# Sheet1.net
KiCad netlist of a schematic drawn in Altium Designer
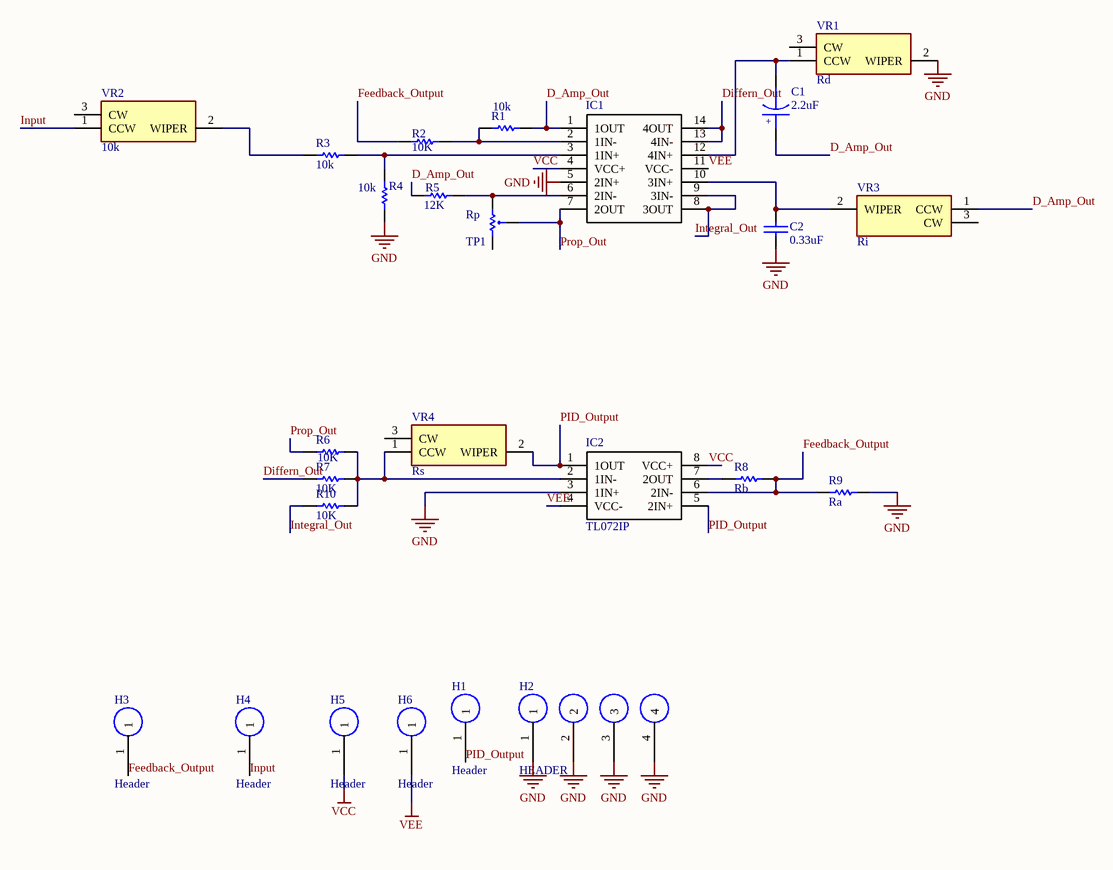
[diagram p0: Sheet1.SchDoc]

(export (version "E")
  (design (tool "Eeschema 10.0.6"))
  (components
    (comp (ref "C1")
      (value "2.2uF")
      (footprint "PCB_Project_PCBparts:RB.1/.2")
      (description "Polarized Cap")
      (libsource (lib "PCB_Project_SCHparts") (part "CAPACITOR POL"))
    )
    (comp (ref "C2")
      (value "0.33uF")
      (footprint "PCB_Project_PCBparts:RAD0.1")
      (description "Non Polarized Cap")
      (libsource (lib "PCB_Project_SCHparts") (part "CAP"))
    )
    (comp (ref "H1")
      (value "Header")
      (footprint "HEADER SINGLE")
      (description "Header single")
      (libsource (lib "PCB_Project_SCHparts") (part "HEADER 1"))
    )
    (comp (ref "H2")
      (value "HEADER")
      (footprint "HEADER QUAD")
      (description "Header quad")
      (libsource (lib "PCB_Project_SCHparts") (part "HEADER 4"))
    )
    (comp (ref "H3")
      (value "Header")
      (footprint "HEADER SINGLE")
      (description "Header single")
      (libsource (lib "PCB_Project_SCHparts") (part "HEADER 1"))
    )
    (comp (ref "H4")
      (value "Header")
      (footprint "HEADER SINGLE")
      (description "Header single")
      (libsource (lib "PCB_Project_SCHparts") (part "HEADER 1"))
    )
    (comp (ref "H5")
      (value "Header")
      (footprint "HEADER SINGLE")
      (description "Header single")
      (libsource (lib "PCB_Project_SCHparts") (part "HEADER 1"))
    )
    (comp (ref "H6")
      (value "Header")
      (footprint "HEADER SINGLE")
      (description "Header single")
      (libsource (lib "PCB_Project_SCHparts") (part "HEADER 1"))
    )
    (comp (ref "IC1")
      (value "~")
      (footprint "DIP794W53P254L1930H508Q14N")
      (description "Integrated Circuit")
      (fields
        (field (name "MANUFACTURER_PART_NUMBER") "TL074CN")
        (field (name "MOUSER PART NUMBER") "511-TL074CN")
      )
      (libsource (lib "PCB_Project_SCHparts_2") (part "TL074CN"))
    )
    (comp (ref "IC2")
      (value "TL072IP")
      (footprint "DIP794W53P254L959H508Q8N")
      (description "Integrated Circuit")
      (fields (field (name "MOUSER PART NUMBER") "595-TL072IP"))
      (libsource (lib "PCB_Project_SCHparts_2") (part "TL072IP"))
    )
    (comp (ref "R1")
      (value "10k")
      (footprint "PCB_Project_PCBparts:AXIAL0.4")
      (description "1/4 W Res")
      (libsource (lib "PCB_Project_SCHparts") (part "RES"))
    )
    (comp (ref "R2")
      (value "10K")
      (footprint "PCB_Project_PCBparts:AXIAL0.4")
      (description "1/4 W Res")
      (libsource (lib "PCB_Project_SCHparts") (part "RES"))
    )
    (comp (ref "R3")
      (value "10k")
      (footprint "PCB_Project_PCBparts:AXIAL0.4")
      (description "1/4 W Res")
      (libsource (lib "PCB_Project_SCHparts") (part "RES"))
    )
    (comp (ref "R4")
      (value "10k")
      (footprint "PCB_Project_PCBparts:AXIAL0.4")
      (description "1/4 W Res")
      (libsource (lib "PCB_Project_SCHparts") (part "RES"))
    )
    (comp (ref "R5")
      (value "12K")
      (footprint "PCB_Project_PCBparts:AXIAL0.4")
      (description "1/4 W Res")
      (libsource (lib "PCB_Project_SCHparts") (part "RES"))
    )
    (comp (ref "R6")
      (value "10K")
      (footprint "PCB_Project_PCBparts:AXIAL0.4")
      (description "1/4 W Res")
      (libsource (lib "PCB_Project_SCHparts") (part "RES"))
    )
    (comp (ref "R7")
      (value "10K")
      (footprint "PCB_Project_PCBparts:AXIAL0.4")
      (description "1/4 W Res")
      (libsource (lib "PCB_Project_SCHparts") (part "RES"))
    )
    (comp (ref "R8")
      (value "Rb")
      (footprint "PCB_Project_PCBparts:AXIAL0.4")
      (description "1/4 W Res")
      (libsource (lib "PCB_Project_SCHparts") (part "RES"))
    )
    (comp (ref "R9")
      (value "Ra")
      (footprint "PCB_Project_PCBparts:AXIAL0.4")
      (description "1/4 W Res")
      (libsource (lib "PCB_Project_SCHparts") (part "RES"))
    )
    (comp (ref "R10")
      (value "10K")
      (footprint "PCB_Project_PCBparts:AXIAL0.4")
      (description "1/4 W Res")
      (libsource (lib "PCB_Project_SCHparts") (part "RES"))
    )
    (comp (ref "TP1")
      (value "Rp")
      (footprint "TRIMPOT")
      (description "Rp=250K")
      (libsource (lib "PCB_Project_SCHparts") (part "TRIMPOT"))
    )
    (comp (ref "VR1")
      (value "Rd")
      (footprint "3386F1104TLF")
      (description "Variable Resistor")
      (fields
        (field (name "MANUFACTURER_PART_NUMBER") "3386F-1-104TLF")
        (field (name "MOUSER PART NUMBER") "652-3386F-1-104TLF")
      )
      (libsource (lib "PCB_Project_SCHparts_2") (part "3386F-1-104TLF"))
    )
    (comp (ref "VR2")
      (value "10k")
      (footprint "3386F1104TLF")
      (description "Variable Resistor")
      (fields
        (field (name "MANUFACTURER_PART_NUMBER") "3386F-1-104TLF")
        (field (name "MOUSER PART NUMBER") "652-3386F-1-104TLF")
      )
      (libsource (lib "PCB_Project_SCHparts_2") (part "3386F-1-104TLF"))
    )
    (comp (ref "VR3")
      (value "Ri")
      (footprint "PCB_Project_PCBparts_2:3386F1104TLF")
      (description "Variable Resistor")
      (fields
        (field (name "MANUFACTURER_PART_NUMBER") "3386F-1-104TLF")
        (field (name "MOUSER PART NUMBER") "652-3386F-1-104TLF")
      )
      (libsource (lib "") (part "3386F-1-104TLF_1"))
    )
    (comp (ref "VR4")
      (value "Rs")
      (footprint "3386F1104TLF")
      (description "Variable Resistor")
      (fields
        (field (name "MANUFACTURER_PART_NUMBER") "3386F-1-104TLF")
        (field (name "MOUSER PART NUMBER") "652-3386F-1-104TLF")
      )
      (libsource (lib "PCB_Project_SCHparts_2") (part "3386F-1-104TLF"))
    )
  )
  (nets
    (net (code "1") (name "/D_Amp_Out") (class "Default")
      (node (ref "C1") (pin "1") (pinfunction "1_1") (pintype "passive"))
      (node (ref "IC1") (pin "1") (pinfunction "1OUT_1") (pintype "passive"))
      (node (ref "R1") (pin "2") (pinfunction "2_2") (pintype "passive"))
      (node (ref "R5") (pin "1") (pinfunction "1_1") (pintype "passive"))
      (node (ref "VR3") (pin "1") (pinfunction "CCW_1") (pintype "passive"))
    )
    (net (code "2") (name "/Differn_Out") (class "Default")
      (node (ref "IC1") (pin "13") (pinfunction "4IN-_13") (pintype "passive"))
      (node (ref "IC1") (pin "14") (pinfunction "4OUT_14") (pintype "passive"))
      (node (ref "R7") (pin "1") (pinfunction "1_1") (pintype "passive"))
    )
    (net (code "3") (name "/Feedback_Output") (class "Default")
      (node (ref "H3") (pin "1") (pinfunction "1_1") (pintype "passive"))
      (node (ref "IC2") (pin "6") (pinfunction "2IN-_6") (pintype "passive"))
      (node (ref "R2") (pin "1") (pinfunction "1_1") (pintype "passive"))
      (node (ref "R8") (pin "2") (pinfunction "2_2") (pintype "passive"))
      (node (ref "R9") (pin "1") (pinfunction "1_1") (pintype "passive"))
    )
    (net (code "4") (name "/Input") (class "Default")
      (node (ref "H4") (pin "1") (pinfunction "1_1") (pintype "passive"))
      (node (ref "VR2") (pin "1") (pinfunction "CCW_1") (pintype "passive"))
    )
    (net (code "5") (name "/Integral_Out") (class "Default")
      (node (ref "IC1") (pin "8") (pinfunction "3OUT_8") (pintype "passive"))
      (node (ref "IC1") (pin "9") (pinfunction "3IN-_9") (pintype "passive"))
      (node (ref "R10") (pin "1") (pinfunction "1_1") (pintype "passive"))
    )
    (net (code "6") (name "/PID_Output") (class "Default")
      (node (ref "H1") (pin "1") (pinfunction "1_1") (pintype "passive"))
      (node (ref "IC2") (pin "1") (pinfunction "1OUT_1") (pintype "passive"))
      (node (ref "IC2") (pin "5") (pinfunction "2IN+_5") (pintype "passive"))
      (node (ref "VR4") (pin "2") (pinfunction "WIPER_2") (pintype "passive"))
    )
    (net (code "7") (name "/Prop_Out") (class "Default")
      (node (ref "IC1") (pin "7") (pinfunction "2OUT_7") (pintype "passive"))
      (node (ref "R6") (pin "1") (pinfunction "1_1") (pintype "passive"))
      (node (ref "TP1") (pin "2") (pinfunction "2_2") (pintype "passive"))
    )
    (net (code "8") (name "GND") (class "Default")
      (node (ref "C2") (pin "1") (pintype "passive"))
      (node (ref "H2") (pin "1") (pinfunction "1_1") (pintype "passive"))
      (node (ref "H2") (pin "2") (pinfunction "2_2") (pintype "passive"))
      (node (ref "H2") (pin "3") (pinfunction "3_3") (pintype "passive"))
      (node (ref "H2") (pin "4") (pinfunction "4_4") (pintype "passive"))
      (node (ref "IC1") (pin "5") (pinfunction "2IN+_5") (pintype "passive"))
      (node (ref "IC2") (pin "3") (pinfunction "1IN+_3") (pintype "passive"))
      (node (ref "R4") (pin "1") (pinfunction "1_1") (pintype "passive"))
      (node (ref "R9") (pin "2") (pinfunction "2_2") (pintype "passive"))
      (node (ref "VR1") (pin "2") (pinfunction "WIPER_2") (pintype "passive"))
    )
    (net (code "9") (name "Net-(IC1-1IN+)") (class "Default")
      (node (ref "IC1") (pin "3") (pinfunction "1IN+_3") (pintype "passive"))
      (node (ref "R3") (pin "2") (pinfunction "2_2") (pintype "passive"))
      (node (ref "R4") (pin "2") (pinfunction "2_2") (pintype "passive"))
    )
    (net (code "10") (name "Net-(IC1-1IN-)") (class "Default")
      (node (ref "IC1") (pin "2") (pinfunction "1IN-_2") (pintype "passive"))
      (node (ref "R1") (pin "1") (pinfunction "1_1") (pintype "passive"))
      (node (ref "R2") (pin "2") (pinfunction "2_2") (pintype "passive"))
    )
    (net (code "11") (name "Net-(IC1-2IN-)") (class "Default")
      (node (ref "IC1") (pin "6") (pinfunction "2IN-_6") (pintype "passive"))
      (node (ref "R5") (pin "2") (pinfunction "2_2") (pintype "passive"))
      (node (ref "TP1") (pin "1") (pinfunction "1_1") (pintype "passive"))
    )
    (net (code "12") (name "Net-(IC1-3IN+)") (class "Default")
      (node (ref "C2") (pin "2") (pintype "passive"))
      (node (ref "IC1") (pin "10") (pinfunction "3IN+_10") (pintype "passive"))
      (node (ref "VR3") (pin "2") (pinfunction "WIPER_2") (pintype "passive"))
    )
    (net (code "13") (name "Net-(IC1-4IN+)") (class "Default")
      (node (ref "C1") (pin "2") (pinfunction "2_2") (pintype "passive"))
      (node (ref "IC1") (pin "12") (pinfunction "4IN+_12") (pintype "passive"))
      (node (ref "VR1") (pin "1") (pinfunction "CCW_1") (pintype "passive"))
    )
    (net (code "14") (name "Net-(IC2-1IN-)") (class "Default")
      (node (ref "IC2") (pin "2") (pinfunction "1IN-_2") (pintype "passive"))
      (node (ref "R10") (pin "2") (pinfunction "2_2") (pintype "passive"))
      (node (ref "R6") (pin "2") (pinfunction "2_2") (pintype "passive"))
      (node (ref "R7") (pin "2") (pinfunction "2_2") (pintype "passive"))
      (node (ref "VR4") (pin "1") (pinfunction "CCW_1") (pintype "passive"))
    )
    (net (code "15") (name "Net-(IC2-2OUT)") (class "Default")
      (node (ref "IC2") (pin "7") (pinfunction "2OUT_7") (pintype "passive"))
      (node (ref "R8") (pin "1") (pinfunction "1_1") (pintype "passive"))
    )
    (net (code "16") (name "Net-(VR2-WIPER)") (class "Default")
      (node (ref "R3") (pin "1") (pinfunction "1_1") (pintype "passive"))
      (node (ref "VR2") (pin "2") (pinfunction "WIPER_2") (pintype "passive"))
    )
    (net (code "17") (name "VCC") (class "Default")
      (node (ref "H5") (pin "1") (pinfunction "1_1") (pintype "passive"))
      (node (ref "IC1") (pin "4") (pinfunction "VCC+_4") (pintype "passive"))
      (node (ref "IC2") (pin "8") (pinfunction "VCC+_8") (pintype "passive"))
    )
    (net (code "18") (name "VEE") (class "Default")
      (node (ref "H6") (pin "1") (pinfunction "1_1") (pintype "passive"))
      (node (ref "IC1") (pin "11") (pinfunction "VCC-_11") (pintype "passive"))
      (node (ref "IC2") (pin "4") (pinfunction "VCC-_4") (pintype "passive"))
    )
    (net (code "19") (name "unconnected-(TP1-Pad3)") (class "Default")
      (node (ref "TP1") (pin "3") (pinfunction "3_3") (pintype "passive"))
    )
    (net (code "20") (name "unconnected-(VR1-CW-Pad3)") (class "Default")
      (node (ref "VR1") (pin "3") (pinfunction "CW_3") (pintype "passive"))
    )
    (net (code "21") (name "unconnected-(VR2-CW-Pad3)") (class "Default")
      (node (ref "VR2") (pin "3") (pinfunction "CW_3") (pintype "passive"))
    )
    (net (code "22") (name "unconnected-(VR3-CW-Pad3)") (class "Default")
      (node (ref "VR3") (pin "3") (pinfunction "CW_3") (pintype "passive"))
    )
    (net (code "23") (name "unconnected-(VR4-CW-Pad3)") (class "Default")
      (node (ref "VR4") (pin "3") (pinfunction "CW_3") (pintype "passive"))
    )
  )
)
